# USB_Wireless_2_4G.net
KiCad netlist of a schematic drawn in Altium Designer
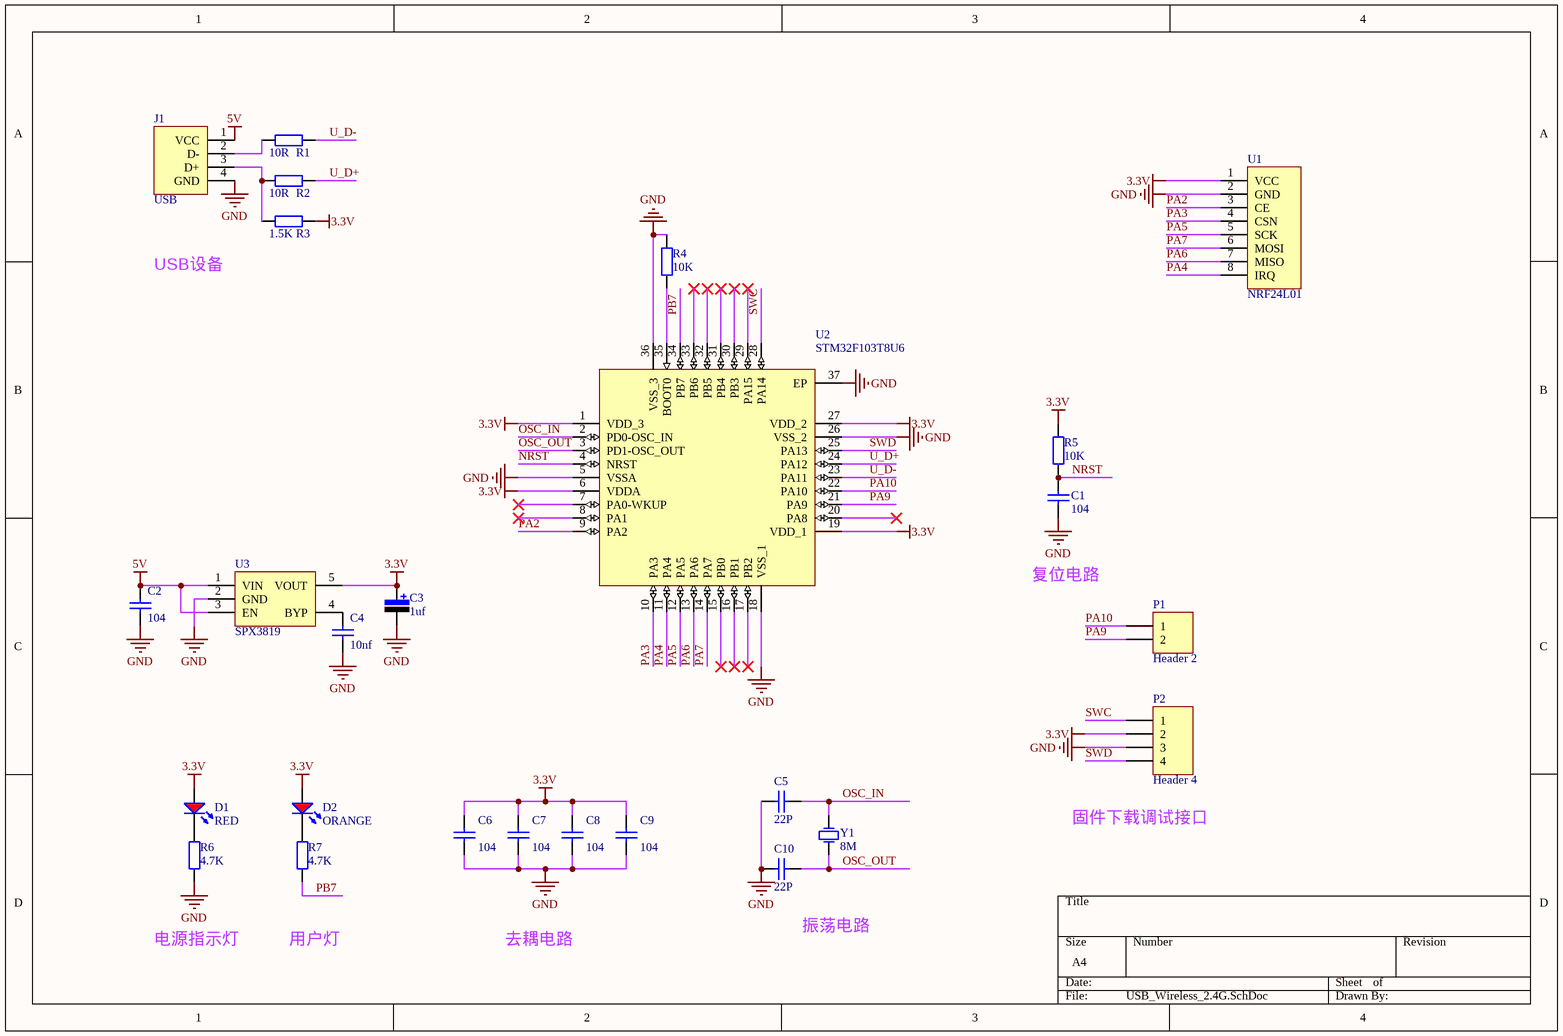
[diagram p0: USB_Wireless_2.4G.SchDoc]

(export (version "E")
  (design (tool "Eeschema 10.0.6"))
  (components
    (comp (ref "C1") (value "104") (footprint "Cap-0603") (libsource (lib "base") (part "Cap")))
    (comp (ref "C2") (value "104") (footprint "Cap-0603") (libsource (lib "base") (part "Cap")))
    (comp (ref "C3") (value "1uf") (footprint "CAP-tan-3216") (libsource (lib "base") (part "Cap+")))
    (comp (ref "C4") (value "10nf") (footprint "Cap-0603") (libsource (lib "base") (part "Cap")))
    (comp (ref "C5") (value "22P") (footprint "Cap-0603") (libsource (lib "base") (part "Cap")))
    (comp (ref "C6") (value "104") (footprint "Cap-0603") (libsource (lib "base") (part "Cap")))
    (comp (ref "C7") (value "104") (footprint "Cap-0603") (libsource (lib "base") (part "Cap")))
    (comp (ref "C8") (value "104") (footprint "Cap-0603") (libsource (lib "base") (part "Cap")))
    (comp (ref "C9") (value "104") (footprint "Cap-0603") (libsource (lib "base") (part "Cap")))
    (comp (ref "C10") (value "22P") (footprint "Cap-0603") (libsource (lib "base") (part "Cap")))
    (comp (ref "D1") (value "RED") (footprint "LED-0603") (libsource (lib "base") (part "LED")))
    (comp (ref "D2") (value "ORANGE") (footprint "LED-0603") (libsource (lib "base") (part "LED")))
    (comp (ref "J1")
      (value "USB")
      (footprint "USB贴片鱼叉型公头")
      (libsource (lib "USB_Wireless_2.4G") (part "USB"))
    )
    (comp (ref "P1")
      (value "Header 2")
      (footprint "HDR1X2")
      (description "Header, 2-Pin")
      (fields (field (name "PUBLISHER") "Altium Limited"))
      (libsource (lib "base") (part "Header 2"))
    )
    (comp (ref "P2")
      (value "Header 4")
      (footprint "HDR1X4")
      (description "Header, 4-Pin")
      (fields (field (name "PUBLISHER") "Altium Limited"))
      (libsource (lib "base") (part "Header 4"))
    )
    (comp (ref "R1") (value "10R") (footprint "Res-0603") (libsource (lib "base") (part "Res")))
    (comp (ref "R2") (value "10R") (footprint "Res-0603") (libsource (lib "base") (part "Res")))
    (comp (ref "R3") (value "1.5K") (footprint "Res-0603") (libsource (lib "base") (part "Res")))
    (comp (ref "R4") (value "10K") (footprint "Res-0603") (libsource (lib "") (part "Res_1")))
    (comp (ref "R5") (value "10K") (footprint "Res-0603") (libsource (lib "") (part "Res_1")))
    (comp (ref "R6") (value "4.7K") (footprint "Res-0603") (libsource (lib "") (part "Res_1")))
    (comp (ref "R7") (value "4.7K") (footprint "Res-0603") (libsource (lib "") (part "Res_1")))
    (comp (ref "U1")
      (value "NRF24L01")
      (footprint "NRF24L01")
      (libsource (lib "USB_Wireless_2.4G") (part "NRF24L01"))
    )
    (comp (ref "U2")
      (value "STM32F103T8U6")
      (footprint "STM-VFQFPN36_L")
      (libsource (lib "USB_Wireless_2.4G") (part "STM32F103T8U6"))
    )
    (comp (ref "U3")
      (value "SPX3819")
      (footprint "SOT23-5")
      (libsource (lib "USB_Wireless_2.4G") (part "SPX3819"))
    )
    (comp (ref "Y1") (value "8M") (footprint "XTAL_8M_5032") (libsource (lib "base") (part "XTAL")))
  )
  (nets
    (net (code "1") (name "/NRST") (class "Default")
      (node (ref "C1") (pin "2") (pinfunction "2_2") (pintype "passive"))
      (node (ref "R5") (pin "1") (pinfunction "1_1") (pintype "passive"))
      (node (ref "U2") (pin "4") (pinfunction "NRST_4") (pintype "bidirectional"))
    )
    (net (code "2") (name "/OSC_IN") (class "Default")
      (node (ref "C5") (pin "2") (pinfunction "2_2") (pintype "passive"))
      (node (ref "U2") (pin "2") (pinfunction "PD0-OSC_IN_2") (pintype "bidirectional"))
      (node (ref "Y1") (pin "1") (pinfunction "OSC1_1") (pintype "passive"))
    )
    (net (code "3") (name "/OSC_OUT") (class "Default")
      (node (ref "C10") (pin "2") (pinfunction "2_2") (pintype "passive"))
      (node (ref "U2") (pin "3") (pinfunction "PD1-OSC_OUT_3") (pintype "bidirectional"))
      (node (ref "Y1") (pin "2") (pinfunction "OSC2_2") (pintype "passive"))
    )
    (net (code "4") (name "/PA2") (class "Default")
      (node (ref "U1") (pin "3") (pinfunction "CE_3") (pintype "power_in"))
      (node (ref "U2") (pin "9") (pinfunction "PA2_9") (pintype "bidirectional"))
    )
    (net (code "5") (name "/PA3") (class "Default")
      (node (ref "U1") (pin "4") (pinfunction "CSN_4") (pintype "power_in"))
      (node (ref "U2") (pin "10") (pinfunction "PA3_10") (pintype "bidirectional"))
    )
    (net (code "6") (name "/PA4") (class "Default")
      (node (ref "U1") (pin "8") (pinfunction "IRQ_8") (pintype "power_in"))
      (node (ref "U2") (pin "11") (pinfunction "PA4_11") (pintype "bidirectional"))
    )
    (net (code "7") (name "/PA5") (class "Default")
      (node (ref "U1") (pin "5") (pinfunction "SCK_5") (pintype "power_in"))
      (node (ref "U2") (pin "12") (pinfunction "PA5_12") (pintype "bidirectional"))
    )
    (net (code "8") (name "/PA6") (class "Default")
      (node (ref "U1") (pin "7") (pinfunction "MISO_7") (pintype "power_in"))
      (node (ref "U2") (pin "13") (pinfunction "PA6_13") (pintype "bidirectional"))
    )
    (net (code "9") (name "/PA7") (class "Default")
      (node (ref "U1") (pin "6") (pinfunction "MOSI_6") (pintype "power_in"))
      (node (ref "U2") (pin "14") (pinfunction "PA7_14") (pintype "bidirectional"))
    )
    (net (code "10") (name "/PA9") (class "Default")
      (node (ref "P1") (pin "2") (pinfunction "2_2") (pintype "passive"))
      (node (ref "U2") (pin "21") (pinfunction "PA9_21") (pintype "bidirectional"))
    )
    (net (code "11") (name "/PA10") (class "Default")
      (node (ref "P1") (pin "1") (pinfunction "1_1") (pintype "passive"))
      (node (ref "U2") (pin "22") (pinfunction "PA10_22") (pintype "bidirectional"))
    )
    (net (code "12") (name "/PB7") (class "Default")
      (node (ref "R7") (pin "1") (pinfunction "1_1") (pintype "passive"))
      (node (ref "U2") (pin "34") (pinfunction "PB7_34") (pintype "bidirectional"))
    )
    (net (code "13") (name "/SWC") (class "Default")
      (node (ref "P2") (pin "1") (pinfunction "1_1") (pintype "passive"))
      (node (ref "U2") (pin "28") (pinfunction "PA14_28") (pintype "bidirectional"))
    )
    (net (code "14") (name "/SWD") (class "Default")
      (node (ref "P2") (pin "4") (pinfunction "4_4") (pintype "passive"))
      (node (ref "U2") (pin "25") (pinfunction "PA13_25") (pintype "bidirectional"))
    )
    (net (code "15") (name "/U_D+") (class "Default")
      (node (ref "R2") (pin "1") (pinfunction "1_1") (pintype "passive"))
      (node (ref "U2") (pin "24") (pinfunction "PA12_24") (pintype "bidirectional"))
    )
    (net (code "16") (name "/U_D-") (class "Default")
      (node (ref "R1") (pin "1") (pinfunction "1_1") (pintype "passive"))
      (node (ref "U2") (pin "23") (pinfunction "PA11_23") (pintype "bidirectional"))
    )
    (net (code "17") (name "3.3V") (class "Default")
      (node (ref "C3") (pin "1") (pinfunction "1_1") (pintype "passive"))
      (node (ref "C6") (pin "2") (pinfunction "2_2") (pintype "passive"))
      (node (ref "C7") (pin "2") (pinfunction "2_2") (pintype "passive"))
      (node (ref "C8") (pin "2") (pinfunction "2_2") (pintype "passive"))
      (node (ref "C9") (pin "2") (pinfunction "2_2") (pintype "passive"))
      (node (ref "D1") (pin "1") (pinfunction "A_1") (pintype "passive"))
      (node (ref "D2") (pin "1") (pinfunction "A_1") (pintype "passive"))
      (node (ref "P2") (pin "2") (pinfunction "2_2") (pintype "passive"))
      (node (ref "R3") (pin "1") (pinfunction "1_1") (pintype "passive"))
      (node (ref "R5") (pin "2") (pinfunction "2_2") (pintype "passive"))
      (node (ref "U1") (pin "1") (pinfunction "VCC_1") (pintype "power_in"))
      (node (ref "U2") (pin "1") (pinfunction "VDD_3_1") (pintype "power_in"))
      (node (ref "U2") (pin "19") (pinfunction "VDD_1_19") (pintype "power_in"))
      (node (ref "U2") (pin "27") (pinfunction "VDD_2_27") (pintype "power_in"))
      (node (ref "U2") (pin "6") (pinfunction "VDDA_6") (pintype "power_in"))
      (node (ref "U3") (pin "5") (pinfunction "VOUT_5") (pintype "power_in"))
    )
    (net (code "18") (name "5V") (class "Default")
      (node (ref "C2") (pin "2") (pinfunction "2_2") (pintype "passive"))
      (node (ref "J1") (pin "1") (pinfunction "VCC_1") (pintype "passive"))
      (node (ref "U3") (pin "1") (pinfunction "VIN_1") (pintype "power_in"))
      (node (ref "U3") (pin "3") (pinfunction "EN_3") (pintype "power_in"))
    )
    (net (code "19") (name "GND") (class "Default")
      (node (ref "C1") (pin "1") (pinfunction "1_1") (pintype "passive"))
      (node (ref "C10") (pin "1") (pinfunction "1_1") (pintype "passive"))
      (node (ref "C2") (pin "1") (pinfunction "1_1") (pintype "passive"))
      (node (ref "C3") (pin "2") (pinfunction "2_2") (pintype "passive"))
      (node (ref "C4") (pin "1") (pinfunction "1_1") (pintype "passive"))
      (node (ref "C5") (pin "1") (pinfunction "1_1") (pintype "passive"))
      (node (ref "C6") (pin "1") (pinfunction "1_1") (pintype "passive"))
      (node (ref "C7") (pin "1") (pinfunction "1_1") (pintype "passive"))
      (node (ref "C8") (pin "1") (pinfunction "1_1") (pintype "passive"))
      (node (ref "C9") (pin "1") (pinfunction "1_1") (pintype "passive"))
      (node (ref "J1") (pin "4") (pinfunction "GND_4") (pintype "passive"))
      (node (ref "P2") (pin "3") (pinfunction "3_3") (pintype "passive"))
      (node (ref "R4") (pin "2") (pinfunction "2_2") (pintype "passive"))
      (node (ref "R6") (pin "1") (pinfunction "1_1") (pintype "passive"))
      (node (ref "U1") (pin "2") (pinfunction "GND_2") (pintype "power_in"))
      (node (ref "U2") (pin "18") (pinfunction "VSS_1_18") (pintype "power_in"))
      (node (ref "U2") (pin "26") (pinfunction "VSS_2_26") (pintype "power_in"))
      (node (ref "U2") (pin "36") (pinfunction "VSS_3_36") (pintype "power_in"))
      (node (ref "U2") (pin "37") (pinfunction "EP_37") (pintype "power_in"))
      (node (ref "U2") (pin "5") (pinfunction "VSSA_5") (pintype "power_in"))
      (node (ref "U3") (pin "2") (pinfunction "GND_2") (pintype "power_in"))
    )
    (net (code "20") (name "Net-(D1-K)") (class "Default")
      (node (ref "D1") (pin "2") (pinfunction "K_2") (pintype "passive"))
      (node (ref "R6") (pin "2") (pinfunction "2_2") (pintype "passive"))
    )
    (net (code "21") (name "Net-(D2-K)") (class "Default")
      (node (ref "D2") (pin "2") (pinfunction "K_2") (pintype "passive"))
      (node (ref "R7") (pin "2") (pinfunction "2_2") (pintype "passive"))
    )
    (net (code "22") (name "Net-(J1-D+)") (class "Default")
      (node (ref "J1") (pin "3") (pinfunction "D+_3") (pintype "passive"))
      (node (ref "R2") (pin "2") (pinfunction "2_2") (pintype "passive"))
      (node (ref "R3") (pin "2") (pinfunction "2_2") (pintype "passive"))
    )
    (net (code "23") (name "Net-(J1-D-)") (class "Default")
      (node (ref "J1") (pin "2") (pinfunction "D-_2") (pintype "passive"))
      (node (ref "R1") (pin "2") (pinfunction "2_2") (pintype "passive"))
    )
    (net (code "24") (name "Net-(U2-BOOT0)") (class "Default")
      (node (ref "R4") (pin "1") (pinfunction "1_1") (pintype "passive"))
      (node (ref "U2") (pin "35") (pinfunction "BOOT0_35") (pintype "input"))
    )
    (net (code "25") (name "Net-(U3-BYP)") (class "Default")
      (node (ref "C4") (pin "2") (pinfunction "2_2") (pintype "passive"))
      (node (ref "U3") (pin "4") (pinfunction "BYP_4") (pintype "power_in"))
    )
    (net (code "26") (name "unconnected-(U2-PA0-WKUP-Pad7)") (class "Default")
      (node (ref "U2") (pin "7") (pinfunction "PA0-WKUP_7") (pintype "bidirectional+no_connect"))
    )
    (net (code "27") (name "unconnected-(U2-PA1-Pad8)") (class "Default")
      (node (ref "U2") (pin "8") (pinfunction "PA1_8") (pintype "bidirectional+no_connect"))
    )
    (net (code "28") (name "unconnected-(U2-PA8-Pad20)") (class "Default")
      (node (ref "U2") (pin "20") (pinfunction "PA8_20") (pintype "bidirectional+no_connect"))
    )
    (net (code "29") (name "unconnected-(U2-PA15-Pad29)") (class "Default")
      (node (ref "U2") (pin "29") (pinfunction "PA15_29") (pintype "bidirectional+no_connect"))
    )
    (net (code "30") (name "unconnected-(U2-PB0-Pad15)") (class "Default")
      (node (ref "U2") (pin "15") (pinfunction "PB0_15") (pintype "bidirectional+no_connect"))
    )
    (net (code "31") (name "unconnected-(U2-PB1-Pad16)") (class "Default")
      (node (ref "U2") (pin "16") (pinfunction "PB1_16") (pintype "bidirectional+no_connect"))
    )
    (net (code "32") (name "unconnected-(U2-PB2-Pad17)") (class "Default")
      (node (ref "U2") (pin "17") (pinfunction "PB2_17") (pintype "bidirectional+no_connect"))
    )
    (net (code "33") (name "unconnected-(U2-PB3-Pad30)") (class "Default")
      (node (ref "U2") (pin "30") (pinfunction "PB3_30") (pintype "bidirectional+no_connect"))
    )
    (net (code "34") (name "unconnected-(U2-PB4-Pad31)") (class "Default")
      (node (ref "U2") (pin "31") (pinfunction "PB4_31") (pintype "bidirectional+no_connect"))
    )
    (net (code "35") (name "unconnected-(U2-PB5-Pad32)") (class "Default")
      (node (ref "U2") (pin "32") (pinfunction "PB5_32") (pintype "bidirectional+no_connect"))
    )
    (net (code "36") (name "unconnected-(U2-PB6-Pad33)") (class "Default")
      (node (ref "U2") (pin "33") (pinfunction "PB6_33") (pintype "bidirectional+no_connect"))
    )
  )
)
